# 3Ph_RC.net
KiCad netlist of a schematic drawn in EAGLE
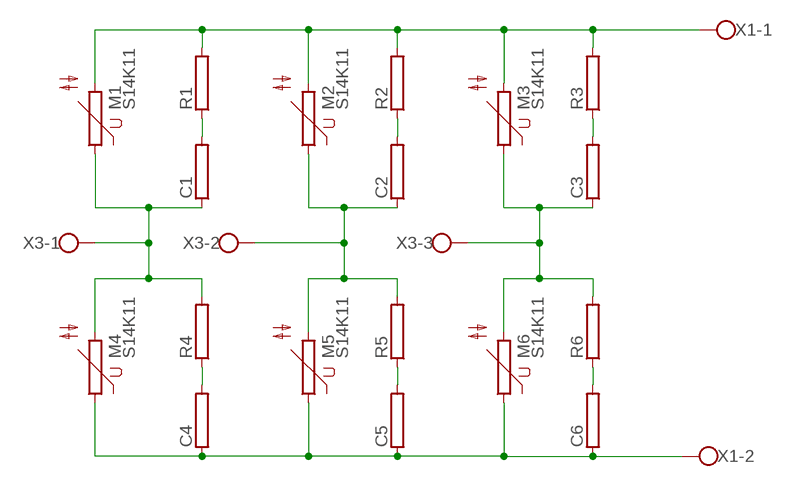
[diagram p0: schematic, sheet 1]

(export (version "E")
  (design (tool "Eeschema 10.0.6"))
  (components
    (comp (ref "C1")
      (value "RRWM8X34")
      (footprint "eagle-import:RWM8X34")
      (libsource (lib "eagle-import") (part "RRWM8X34"))
    )
    (comp (ref "C2")
      (value "RRWM8X34")
      (footprint "eagle-import:RWM8X34")
      (libsource (lib "eagle-import") (part "RRWM8X34"))
    )
    (comp (ref "C3")
      (value "RRWM8X34")
      (footprint "eagle-import:RWM8X34")
      (libsource (lib "eagle-import") (part "RRWM8X34"))
    )
    (comp (ref "C4")
      (value "RRWM8X34")
      (footprint "eagle-import:RWM8X34")
      (libsource (lib "eagle-import") (part "RRWM8X34"))
    )
    (comp (ref "C5")
      (value "RRWM8X34")
      (footprint "eagle-import:RWM8X34")
      (libsource (lib "eagle-import") (part "RRWM8X34"))
    )
    (comp (ref "C6")
      (value "RRWM8X34")
      (footprint "eagle-import:RWM8X34")
      (libsource (lib "eagle-import") (part "RRWM8X34"))
    )
    (comp (ref "M1")
      (value "S14K11")
      (footprint "eagle-import:S14K11")
      (libsource (lib "eagle-import") (part "S14K11"))
    )
    (comp (ref "M2")
      (value "S14K11")
      (footprint "eagle-import:S14K11")
      (libsource (lib "eagle-import") (part "S14K11"))
    )
    (comp (ref "M3")
      (value "S14K11")
      (footprint "eagle-import:S14K11")
      (libsource (lib "eagle-import") (part "S14K11"))
    )
    (comp (ref "M4")
      (value "S14K11")
      (footprint "eagle-import:S14K11")
      (libsource (lib "eagle-import") (part "S14K11"))
    )
    (comp (ref "M5")
      (value "S14K11")
      (footprint "eagle-import:S14K11")
      (libsource (lib "eagle-import") (part "S14K11"))
    )
    (comp (ref "M6")
      (value "S14K11")
      (footprint "eagle-import:S14K11")
      (libsource (lib "eagle-import") (part "S14K11"))
    )
    (comp (ref "R1")
      (value "RRWM10X45")
      (footprint "eagle-import:RWM10X45")
      (libsource (lib "eagle-import") (part "RRWM10X45"))
    )
    (comp (ref "R2")
      (value "RRWM10X45")
      (footprint "eagle-import:RWM10X45")
      (libsource (lib "eagle-import") (part "RRWM10X45"))
    )
    (comp (ref "R3")
      (value "RRWM10X45")
      (footprint "eagle-import:RWM10X45")
      (libsource (lib "eagle-import") (part "RRWM10X45"))
    )
    (comp (ref "R4")
      (value "RRWM10X45")
      (footprint "eagle-import:RWM10X45")
      (libsource (lib "eagle-import") (part "RRWM10X45"))
    )
    (comp (ref "R5")
      (value "RRWM10X45")
      (footprint "eagle-import:RWM10X45")
      (libsource (lib "eagle-import") (part "RRWM10X45"))
    )
    (comp (ref "R6")
      (value "RRWM10X45")
      (footprint "eagle-import:RWM10X45")
      (libsource (lib "eagle-import") (part "RRWM10X45"))
    )
    (comp (ref "X1")
      (value "W237-102")
      (footprint "eagle-import:W237-102")
      (fields (field (name "MPN") "237-102"))
      (libsource (lib "eagle-import") (part "W237-102"))
    )
    (comp (ref "X3")
      (value "W237-103")
      (footprint "eagle-import:W237-103")
      (fields (field (name "MPN") "237-103"))
      (libsource (lib "eagle-import") (part "W237-103"))
    )
  )
  (nets
    (net (code "1") (name "Net-(C1-Pad2)") (class "Default")
      (node (ref "C1") (pin "2") (pinfunction "2_2") (pintype "passive"))
      (node (ref "R1") (pin "1") (pinfunction "1_1") (pintype "passive"))
    )
    (net (code "2") (name "Net-(C2-Pad2)") (class "Default")
      (node (ref "C2") (pin "2") (pinfunction "2_2") (pintype "passive"))
      (node (ref "R2") (pin "1") (pinfunction "1_1") (pintype "passive"))
    )
    (net (code "3") (name "Net-(C3-Pad2)") (class "Default")
      (node (ref "C3") (pin "2") (pinfunction "2_2") (pintype "passive"))
      (node (ref "R3") (pin "1") (pinfunction "1_1") (pintype "passive"))
    )
    (net (code "4") (name "Net-(C4-Pad2)") (class "Default")
      (node (ref "C4") (pin "2") (pinfunction "2_2") (pintype "passive"))
      (node (ref "R4") (pin "1") (pinfunction "1_1") (pintype "passive"))
    )
    (net (code "5") (name "Net-(C5-Pad2)") (class "Default")
      (node (ref "C5") (pin "2") (pinfunction "2_2") (pintype "passive"))
      (node (ref "R5") (pin "1") (pinfunction "1_1") (pintype "passive"))
    )
    (net (code "6") (name "Net-(C6-Pad2)") (class "Default")
      (node (ref "C6") (pin "2") (pinfunction "2_2") (pintype "passive"))
      (node (ref "R6") (pin "1") (pinfunction "1_1") (pintype "passive"))
    )
    (net (code "7") (name "Net-(X1A-KL)") (class "Default")
      (node (ref "M1") (pin "2") (pinfunction "2_2") (pintype "passive"))
      (node (ref "M2") (pin "2") (pinfunction "2_2") (pintype "passive"))
      (node (ref "M3") (pin "2") (pinfunction "2_2") (pintype "passive"))
      (node (ref "R1") (pin "2") (pinfunction "2_2") (pintype "passive"))
      (node (ref "R2") (pin "2") (pinfunction "2_2") (pintype "passive"))
      (node (ref "R3") (pin "2") (pinfunction "2_2") (pintype "passive"))
      (node (ref "X1") (pin "1") (pinfunction "KL_1") (pintype "passive"))
    )
    (net (code "8") (name "Net-(X1B-KL)") (class "Default")
      (node (ref "C4") (pin "1") (pinfunction "1_1") (pintype "passive"))
      (node (ref "C5") (pin "1") (pinfunction "1_1") (pintype "passive"))
      (node (ref "C6") (pin "1") (pinfunction "1_1") (pintype "passive"))
      (node (ref "M4") (pin "1") (pinfunction "1_1") (pintype "passive"))
      (node (ref "M5") (pin "1") (pinfunction "1_1") (pintype "passive"))
      (node (ref "M6") (pin "1") (pinfunction "1_1") (pintype "passive"))
      (node (ref "X1") (pin "2") (pinfunction "KL_2") (pintype "passive"))
    )
    (net (code "9") (name "Net-(X3A-KL)") (class "Default")
      (node (ref "C1") (pin "1") (pinfunction "1_1") (pintype "passive"))
      (node (ref "M1") (pin "1") (pinfunction "1_1") (pintype "passive"))
      (node (ref "M4") (pin "2") (pinfunction "2_2") (pintype "passive"))
      (node (ref "R4") (pin "2") (pinfunction "2_2") (pintype "passive"))
      (node (ref "X3") (pin "1") (pinfunction "KL_1") (pintype "passive"))
    )
    (net (code "10") (name "Net-(X3B-KL)") (class "Default")
      (node (ref "C2") (pin "1") (pinfunction "1_1") (pintype "passive"))
      (node (ref "M2") (pin "1") (pinfunction "1_1") (pintype "passive"))
      (node (ref "M5") (pin "2") (pinfunction "2_2") (pintype "passive"))
      (node (ref "R5") (pin "2") (pinfunction "2_2") (pintype "passive"))
      (node (ref "X3") (pin "2") (pinfunction "KL_2") (pintype "passive"))
    )
    (net (code "11") (name "Net-(X3C-KL)") (class "Default")
      (node (ref "C3") (pin "1") (pinfunction "1_1") (pintype "passive"))
      (node (ref "M3") (pin "1") (pinfunction "1_1") (pintype "passive"))
      (node (ref "M6") (pin "2") (pinfunction "2_2") (pintype "passive"))
      (node (ref "R6") (pin "2") (pinfunction "2_2") (pintype "passive"))
      (node (ref "X3") (pin "3") (pinfunction "KL_3") (pintype "passive"))
    )
  )
)
